# PCB2_forDIY.net
KiCad netlist of a schematic drawn in EAGLE
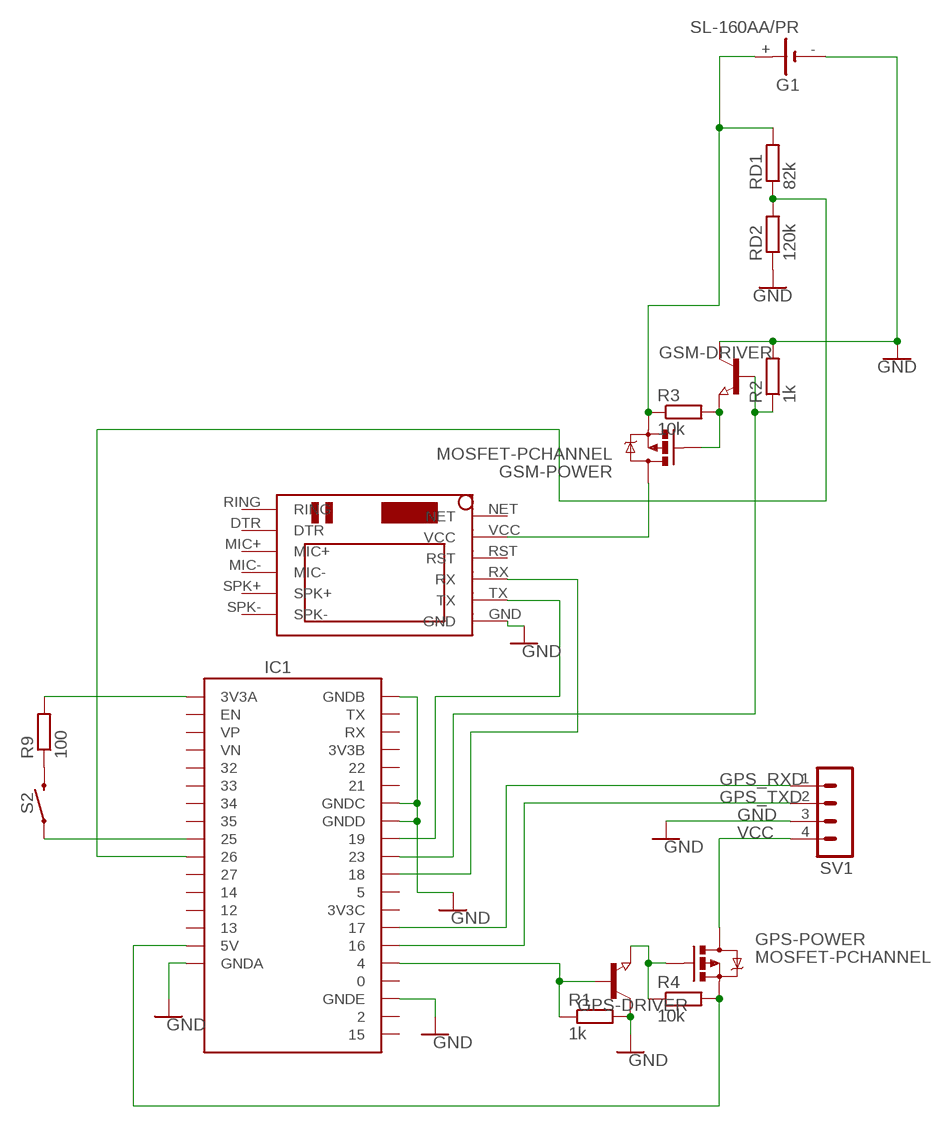
[diagram p0: schematic, sheet 1]

(export (version "E")
  (design (tool "Eeschema 10.0.6"))
  (components
    (comp (ref "G1")
      (value "SL-160AA/PR")
      (footprint "eagle-import:SL-160AA_PR")
      (libsource (lib "eagle-import") (part "SL-160AA/PR"))
    )
    (comp (ref "GPS-DRIVER")
      (value "NPN-TRANSISTOR_SOT23")
      (footprint "eagle-import:SOT23")
      (libsource (lib "eagle-import") (part "NPN-TRANSISTOR_SOT23"))
    )
    (comp (ref "GPS-POWER")
      (value "MOSFET-PCHANNEL")
      (footprint "eagle-import:SOT23-3")
      (libsource (lib "eagle-import") (part "MOSFET-PCHANNEL"))
    )
    (comp (ref "GSM-DRIVER")
      (value "NPN-TRANSISTOR_SOT23")
      (footprint "eagle-import:SOT23")
      (libsource (lib "eagle-import") (part "NPN-TRANSISTOR_SOT23"))
    )
    (comp (ref "GSM-POWER")
      (value "MOSFET-PCHANNEL")
      (footprint "eagle-import:SOT23-3")
      (libsource (lib "eagle-import") (part "MOSFET-PCHANNEL"))
    )
    (comp (ref "IC1")
      (value "SSFD_LOLIN32_WEMOS_CHINA_W_BATT")
      (footprint "eagle-import:SSFD_LOLIN32_WEMOS_CHINA_W_BATT")
      (libsource (lib "eagle-import") (part "SSFD_LOLIN32_WEMOS_CHINA_W_BATT"))
    )
    (comp (ref "R1")
      (value "1k")
      (footprint "eagle-import:R0402")
      (libsource (lib "eagle-import") (part "RR0402"))
    )
    (comp (ref "R2")
      (value "1k")
      (footprint "eagle-import:R0402")
      (libsource (lib "eagle-import") (part "RR0402"))
    )
    (comp (ref "R3")
      (value "10k")
      (footprint "eagle-import:R0603")
      (libsource (lib "eagle-import") (part "RR0603"))
    )
    (comp (ref "R4")
      (value "10k")
      (footprint "eagle-import:R0603")
      (libsource (lib "eagle-import") (part "RR0603"))
    )
    (comp (ref "R9")
      (value "100")
      (footprint "eagle-import:R0603")
      (libsource (lib "eagle-import") (part "RR0603"))
    )
    (comp (ref "RD1")
      (value "82k")
      (footprint "eagle-import:R0402")
      (libsource (lib "eagle-import") (part "RR0402"))
    )
    (comp (ref "RD2")
      (value "120k")
      (footprint "eagle-import:R0402")
      (libsource (lib "eagle-import") (part "RR0402"))
    )
    (comp (ref "S2")
      (value "MOMENTARY-SWITCH-SPST-SMD-6.0X3.5MM")
      (footprint "eagle-import:TACTILE_SWITCH_SMD_6.0X3.5MM")
      (libsource (lib "eagle-import") (part "MOMENTARY-SWITCH-SPST-SMD-6.0X3.5MM"))
    )
    (comp (ref "SV1")
      (value "MA04-1")
      (footprint "eagle-import:MA04-1")
      (libsource (lib "eagle-import") (part "MA04-1"))
    )
    (comp (ref "U$1")
      (value "SIM800LMODULE")
      (footprint "eagle-import:SIM800LMODULE")
      (libsource (lib "eagle-import") (part "SIM800LMODULE"))
    )
  )
  (nets
    (net (code "1") (name "/GPS_RXD") (class "Default")
      (node (ref "IC1") (pin "17") (pinfunction "17_17") (pintype "bidirectional"))
      (node (ref "SV1") (pin "1") (pinfunction "1_1") (pintype "passive"))
    )
    (net (code "2") (name "/GPS_TXD") (class "Default")
      (node (ref "IC1") (pin "16") (pinfunction "16_16") (pintype "bidirectional"))
      (node (ref "SV1") (pin "2") (pinfunction "2_2") (pintype "passive"))
    )
    (net (code "3") (name "/VCC") (class "Default")
      (node (ref "GPS-POWER") (pin "3") (pinfunction "D_3") (pintype "passive"))
      (node (ref "SV1") (pin "4") (pinfunction "4_4") (pintype "passive"))
    )
    (net (code "4") (name "GND") (class "Default")
      (node (ref "G1") (pin "-") (pinfunction "-_-") (pintype "passive"))
      (node (ref "GPS-DRIVER") (pin "3") (pinfunction "C_3") (pintype "passive"))
      (node (ref "GSM-DRIVER") (pin "3") (pinfunction "C_3") (pintype "passive"))
      (node (ref "IC1") (pin "GNDA") (pinfunction "GNDA_GNDA") (pintype "bidirectional"))
      (node (ref "IC1") (pin "GNDB") (pinfunction "GNDB_GNDB") (pintype "bidirectional"))
      (node (ref "IC1") (pin "GNDC") (pinfunction "GNDC_GNDC") (pintype "bidirectional"))
      (node (ref "IC1") (pin "GNDD") (pinfunction "GNDD_GNDD") (pintype "bidirectional"))
      (node (ref "IC1") (pin "GNDE") (pinfunction "GNDE_GNDE") (pintype "bidirectional"))
      (node (ref "R1") (pin "2") (pinfunction "2_2") (pintype "passive"))
      (node (ref "R2") (pin "2") (pinfunction "2_2") (pintype "passive"))
      (node (ref "RD2") (pin "1") (pinfunction "1_1") (pintype "passive"))
      (node (ref "SV1") (pin "3") (pinfunction "3_3") (pintype "passive"))
      (node (ref "U$1") (pin "GND") (pinfunction "GND_GND") (pintype "bidirectional"))
    )
    (net (code "5") (name "Net-(GPS-DRIVER-B)") (class "Default")
      (node (ref "GPS-DRIVER") (pin "1") (pinfunction "B_1") (pintype "passive"))
      (node (ref "IC1") (pin "4") (pinfunction "4_4") (pintype "bidirectional"))
      (node (ref "R1") (pin "1") (pinfunction "1_1") (pintype "passive"))
    )
    (net (code "6") (name "Net-(GPS-DRIVER-E)") (class "Default")
      (node (ref "GPS-DRIVER") (pin "2") (pinfunction "E_2") (pintype "passive"))
      (node (ref "GPS-POWER") (pin "1") (pinfunction "G_1") (pintype "passive"))
      (node (ref "R4") (pin "1") (pinfunction "1_1") (pintype "passive"))
    )
    (net (code "7") (name "Net-(GPS-POWER-S)") (class "Default")
      (node (ref "GPS-POWER") (pin "2") (pinfunction "S_2") (pintype "passive"))
      (node (ref "IC1") (pin "5V") (pinfunction "5V_5V") (pintype "bidirectional"))
      (node (ref "R4") (pin "2") (pinfunction "2_2") (pintype "passive"))
    )
    (net (code "8") (name "Net-(GSM-DRIVER-B)") (class "Default")
      (node (ref "GSM-DRIVER") (pin "1") (pinfunction "B_1") (pintype "passive"))
      (node (ref "IC1") (pin "23") (pinfunction "23_23") (pintype "bidirectional"))
      (node (ref "R2") (pin "1") (pinfunction "1_1") (pintype "passive"))
    )
    (net (code "9") (name "Net-(GSM-DRIVER-E)") (class "Default")
      (node (ref "GSM-DRIVER") (pin "2") (pinfunction "E_2") (pintype "passive"))
      (node (ref "GSM-POWER") (pin "1") (pinfunction "G_1") (pintype "passive"))
      (node (ref "R3") (pin "2") (pinfunction "2_2") (pintype "passive"))
    )
    (net (code "10") (name "Net-(GSM-POWER-D)") (class "Default")
      (node (ref "GSM-POWER") (pin "3") (pinfunction "D_3") (pintype "passive"))
      (node (ref "U$1") (pin "VCC") (pinfunction "VCC_VCC") (pintype "bidirectional"))
    )
    (net (code "11") (name "Net-(GSM-POWER-S)") (class "Default")
      (node (ref "G1") (pin "+") (pinfunction "+_+") (pintype "passive"))
      (node (ref "GSM-POWER") (pin "2") (pinfunction "S_2") (pintype "passive"))
      (node (ref "R3") (pin "1") (pinfunction "1_1") (pintype "passive"))
      (node (ref "RD1") (pin "2") (pinfunction "2_2") (pintype "passive"))
    )
    (net (code "12") (name "Net-(IC1-Pad3V3A)") (class "Default")
      (node (ref "IC1") (pin "3V3A") (pinfunction "3V3A_3V3A") (pintype "bidirectional"))
      (node (ref "R9") (pin "2") (pinfunction "2_2") (pintype "passive"))
    )
    (net (code "13") (name "Net-(IC1-Pad18)") (class "Default")
      (node (ref "IC1") (pin "18") (pinfunction "18_18") (pintype "bidirectional"))
      (node (ref "U$1") (pin "RX") (pinfunction "RX_RX") (pintype "bidirectional"))
    )
    (net (code "14") (name "Net-(IC1-Pad19)") (class "Default")
      (node (ref "IC1") (pin "19") (pinfunction "19_19") (pintype "bidirectional"))
      (node (ref "U$1") (pin "TX") (pinfunction "TX_TX") (pintype "bidirectional"))
    )
    (net (code "15") (name "Net-(IC1-Pad25)") (class "Default")
      (node (ref "IC1") (pin "25") (pinfunction "25_25") (pintype "bidirectional"))
      (node (ref "S2") (pin "1") (pinfunction "1_1") (pintype "passive"))
    )
    (net (code "16") (name "Net-(IC1-Pad26)") (class "Default")
      (node (ref "IC1") (pin "26") (pinfunction "26_26") (pintype "bidirectional"))
      (node (ref "RD1") (pin "1") (pinfunction "1_1") (pintype "passive"))
      (node (ref "RD2") (pin "2") (pinfunction "2_2") (pintype "passive"))
    )
    (net (code "17") (name "Net-(R9-Pad1)") (class "Default")
      (node (ref "R9") (pin "1") (pinfunction "1_1") (pintype "passive"))
      (node (ref "S2") (pin "2") (pinfunction "2_2") (pintype "passive"))
    )
    (net (code "18") (name "unconnected-(IC1-Pad0)") (class "Default")
      (node (ref "IC1") (pin "0") (pinfunction "0_0") (pintype "bidirectional"))
    )
    (net (code "19") (name "unconnected-(IC1-Pad2)") (class "Default")
      (node (ref "IC1") (pin "2") (pinfunction "2_2") (pintype "bidirectional"))
    )
    (net (code "20") (name "unconnected-(IC1-Pad3V3B)") (class "Default")
      (node (ref "IC1") (pin "3V3B") (pinfunction "3V3B_3V3B") (pintype "bidirectional"))
    )
    (net (code "21") (name "unconnected-(IC1-Pad3V3C)") (class "Default")
      (node (ref "IC1") (pin "3V3C") (pinfunction "3V3C_3V3C") (pintype "bidirectional"))
    )
    (net (code "22") (name "unconnected-(IC1-Pad5)") (class "Default")
      (node (ref "IC1") (pin "5") (pinfunction "5_5") (pintype "bidirectional"))
    )
    (net (code "23") (name "unconnected-(IC1-Pad12)") (class "Default")
      (node (ref "IC1") (pin "12") (pinfunction "12_12") (pintype "bidirectional"))
    )
    (net (code "24") (name "unconnected-(IC1-Pad13)") (class "Default")
      (node (ref "IC1") (pin "13") (pinfunction "13_13") (pintype "bidirectional"))
    )
    (net (code "25") (name "unconnected-(IC1-Pad14)") (class "Default")
      (node (ref "IC1") (pin "14") (pinfunction "14_14") (pintype "bidirectional"))
    )
    (net (code "26") (name "unconnected-(IC1-Pad15)") (class "Default")
      (node (ref "IC1") (pin "15") (pinfunction "15_15") (pintype "bidirectional"))
    )
    (net (code "27") (name "unconnected-(IC1-Pad21)") (class "Default")
      (node (ref "IC1") (pin "21") (pinfunction "21_21") (pintype "bidirectional"))
    )
    (net (code "28") (name "unconnected-(IC1-Pad22)") (class "Default")
      (node (ref "IC1") (pin "22") (pinfunction "22_22") (pintype "bidirectional"))
    )
    (net (code "29") (name "unconnected-(IC1-Pad27)") (class "Default")
      (node (ref "IC1") (pin "27") (pinfunction "27_27") (pintype "bidirectional"))
    )
    (net (code "30") (name "unconnected-(IC1-Pad32)") (class "Default")
      (node (ref "IC1") (pin "32") (pinfunction "32_32") (pintype "bidirectional"))
    )
    (net (code "31") (name "unconnected-(IC1-Pad33)") (class "Default")
      (node (ref "IC1") (pin "33") (pinfunction "33_33") (pintype "bidirectional"))
    )
    (net (code "32") (name "unconnected-(IC1-Pad34)") (class "Default")
      (node (ref "IC1") (pin "34") (pinfunction "34_34") (pintype "bidirectional"))
    )
    (net (code "33") (name "unconnected-(IC1-Pad35)") (class "Default")
      (node (ref "IC1") (pin "35") (pinfunction "35_35") (pintype "bidirectional"))
    )
    (net (code "34") (name "unconnected-(IC1-PadEN)") (class "Default")
      (node (ref "IC1") (pin "EN") (pinfunction "EN_EN") (pintype "bidirectional"))
    )
    (net (code "35") (name "unconnected-(IC1-PadRX)") (class "Default")
      (node (ref "IC1") (pin "RX") (pinfunction "RX_RX") (pintype "bidirectional"))
    )
    (net (code "36") (name "unconnected-(IC1-PadTX)") (class "Default")
      (node (ref "IC1") (pin "TX") (pinfunction "TX_TX") (pintype "bidirectional"))
    )
    (net (code "37") (name "unconnected-(IC1-PadVN)") (class "Default")
      (node (ref "IC1") (pin "VN") (pinfunction "VN_VN") (pintype "bidirectional"))
    )
    (net (code "38") (name "unconnected-(IC1-PadVP)") (class "Default")
      (node (ref "IC1") (pin "VP") (pinfunction "VP_VP") (pintype "bidirectional"))
    )
    (net (code "39") (name "unconnected-(U$1-PadDTR)") (class "Default")
      (node (ref "U$1") (pin "DTR") (pinfunction "DTR_DTR") (pintype "bidirectional"))
    )
    (net (code "40") (name "unconnected-(U$1-PadMIC+)") (class "Default")
      (node (ref "U$1") (pin "MIC+") (pinfunction "MIC+_MIC+") (pintype "bidirectional"))
    )
    (net (code "41") (name "unconnected-(U$1-PadMIC-)") (class "Default")
      (node (ref "U$1") (pin "MIC-") (pinfunction "MIC-_MIC-") (pintype "bidirectional"))
    )
    (net (code "42") (name "unconnected-(U$1-PadNET)") (class "Default")
      (node (ref "U$1") (pin "NET") (pinfunction "NET_NET") (pintype "bidirectional"))
    )
    (net (code "43") (name "unconnected-(U$1-PadRING)") (class "Default")
      (node (ref "U$1") (pin "RING") (pinfunction "RING_RING") (pintype "bidirectional"))
    )
    (net (code "44") (name "unconnected-(U$1-PadRST)") (class "Default")
      (node (ref "U$1") (pin "RST") (pinfunction "RST_RST") (pintype "bidirectional"))
    )
    (net (code "45") (name "unconnected-(U$1-PadSPK+)") (class "Default")
      (node (ref "U$1") (pin "SPK+") (pinfunction "SPK+_SPK+") (pintype "bidirectional"))
    )
    (net (code "46") (name "unconnected-(U$1-PadSPK-)") (class "Default")
      (node (ref "U$1") (pin "SPK-") (pinfunction "SPK-_SPK-") (pintype "bidirectional"))
    )
  )
)
